# charLED44inchess.net
KiCad netlist of a schematic drawn in EAGLE
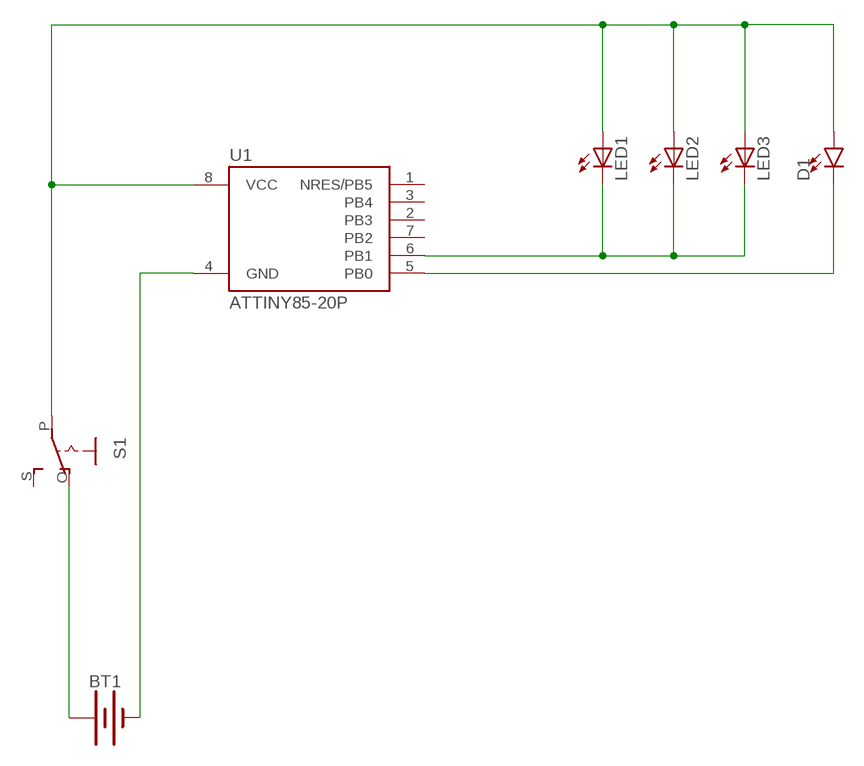
[diagram p0: schematic, sheet 1]

(export (version "E")
  (design (tool "Eeschema 10.0.6"))
  (components
    (comp (ref "BT1")
      (value "BATTERY-20MM_PTH")
      (footprint "eagle-import:BATTCOM_20MM_PTH")
      (libsource (lib "eagle-import") (part "BATTERY-20MM_PTH"))
    )
    (comp (ref "D1")
      (value "LED3MM")
      (footprint "eagle-import:LED_3MM")
      (libsource (lib "eagle-import") (part "LED3MM"))
    )
    (comp (ref "LED1")
      (value "LED5MM")
      (footprint "eagle-import:LED5MM")
      (libsource (lib "eagle-import") (part "adafruit_LED5MM"))
    )
    (comp (ref "LED2")
      (value "LED5MM")
      (footprint "eagle-import:LED5MM")
      (libsource (lib "eagle-import") (part "adafruit_LED5MM"))
    )
    (comp (ref "LED3")
      (value "LED5MM")
      (footprint "eagle-import:LED5MM")
      (libsource (lib "eagle-import") (part "adafruit_LED5MM"))
    )
    (comp (ref "S1")
      (value "EG1218S")
      (footprint "eagle-import:EG1218")
      (libsource (lib "eagle-import") (part "EG1218S"))
    )
    (comp (ref "U1")
      (value "ATTINY85-20P")
      (footprint "eagle-import:PDIP08_300MIL")
      (libsource (lib "eagle-import") (part "ATTINY85P-20"))
    )
  )
  (nets
    (net (code "1") (name "Net-(BT1-+)") (class "Default")
      (node (ref "BT1") (pin "1") (pinfunction "+_1") (pintype "power_in"))
      (node (ref "S1") (pin "O") (pinfunction "O_O") (pintype "passive"))
    )
    (net (code "2") (name "Net-(BT1--)") (class "Default")
      (node (ref "BT1") (pin "2") (pinfunction "-_2") (pintype "power_in"))
      (node (ref "U1") (pin "4") (pinfunction "GND_4") (pintype "power_in"))
    )
    (net (code "3") (name "Net-(D1-C)") (class "Default")
      (node (ref "D1") (pin "K") (pinfunction "C_K") (pintype "passive"))
      (node (ref "U1") (pin "5") (pinfunction "PB0_5") (pintype "bidirectional"))
    )
    (net (code "4") (name "Net-(LED1-C)") (class "Default")
      (node (ref "LED1") (pin "K") (pinfunction "C_K") (pintype "passive"))
      (node (ref "LED2") (pin "K") (pinfunction "C_K") (pintype "passive"))
      (node (ref "LED3") (pin "K") (pinfunction "C_K") (pintype "passive"))
      (node (ref "U1") (pin "6") (pinfunction "PB1_6") (pintype "bidirectional"))
    )
    (net (code "5") (name "Net-(U1-VCC)") (class "Default")
      (node (ref "D1") (pin "A") (pinfunction "A_A") (pintype "passive"))
      (node (ref "LED1") (pin "A") (pinfunction "A_A") (pintype "passive"))
      (node (ref "LED2") (pin "A") (pinfunction "A_A") (pintype "passive"))
      (node (ref "LED3") (pin "A") (pinfunction "A_A") (pintype "passive"))
      (node (ref "S1") (pin "P") (pinfunction "P_P") (pintype "passive"))
      (node (ref "U1") (pin "8") (pinfunction "VCC_8") (pintype "power_in"))
    )
    (net (code "6") (name "unconnected-(S1-PadS)") (class "Default")
      (node (ref "S1") (pin "S") (pinfunction "S_S") (pintype "passive"))
    )
    (net (code "7") (name "unconnected-(U1-NRES{slash}PB5-Pad1)") (class "Default")
      (node (ref "U1") (pin "1") (pinfunction "NRES/PB5_1") (pintype "bidirectional"))
    )
    (net (code "8") (name "unconnected-(U1-PB2-Pad7)") (class "Default")
      (node (ref "U1") (pin "7") (pinfunction "PB2_7") (pintype "bidirectional"))
    )
    (net (code "9") (name "unconnected-(U1-PB3-Pad2)") (class "Default")
      (node (ref "U1") (pin "2") (pinfunction "PB3_2") (pintype "bidirectional"))
    )
    (net (code "10") (name "unconnected-(U1-PB4-Pad3)") (class "Default")
      (node (ref "U1") (pin "3") (pinfunction "PB4_3") (pintype "bidirectional"))
    )
  )
)
